# PongSat_Sen3.net
KiCad netlist of a schematic drawn in EAGLE
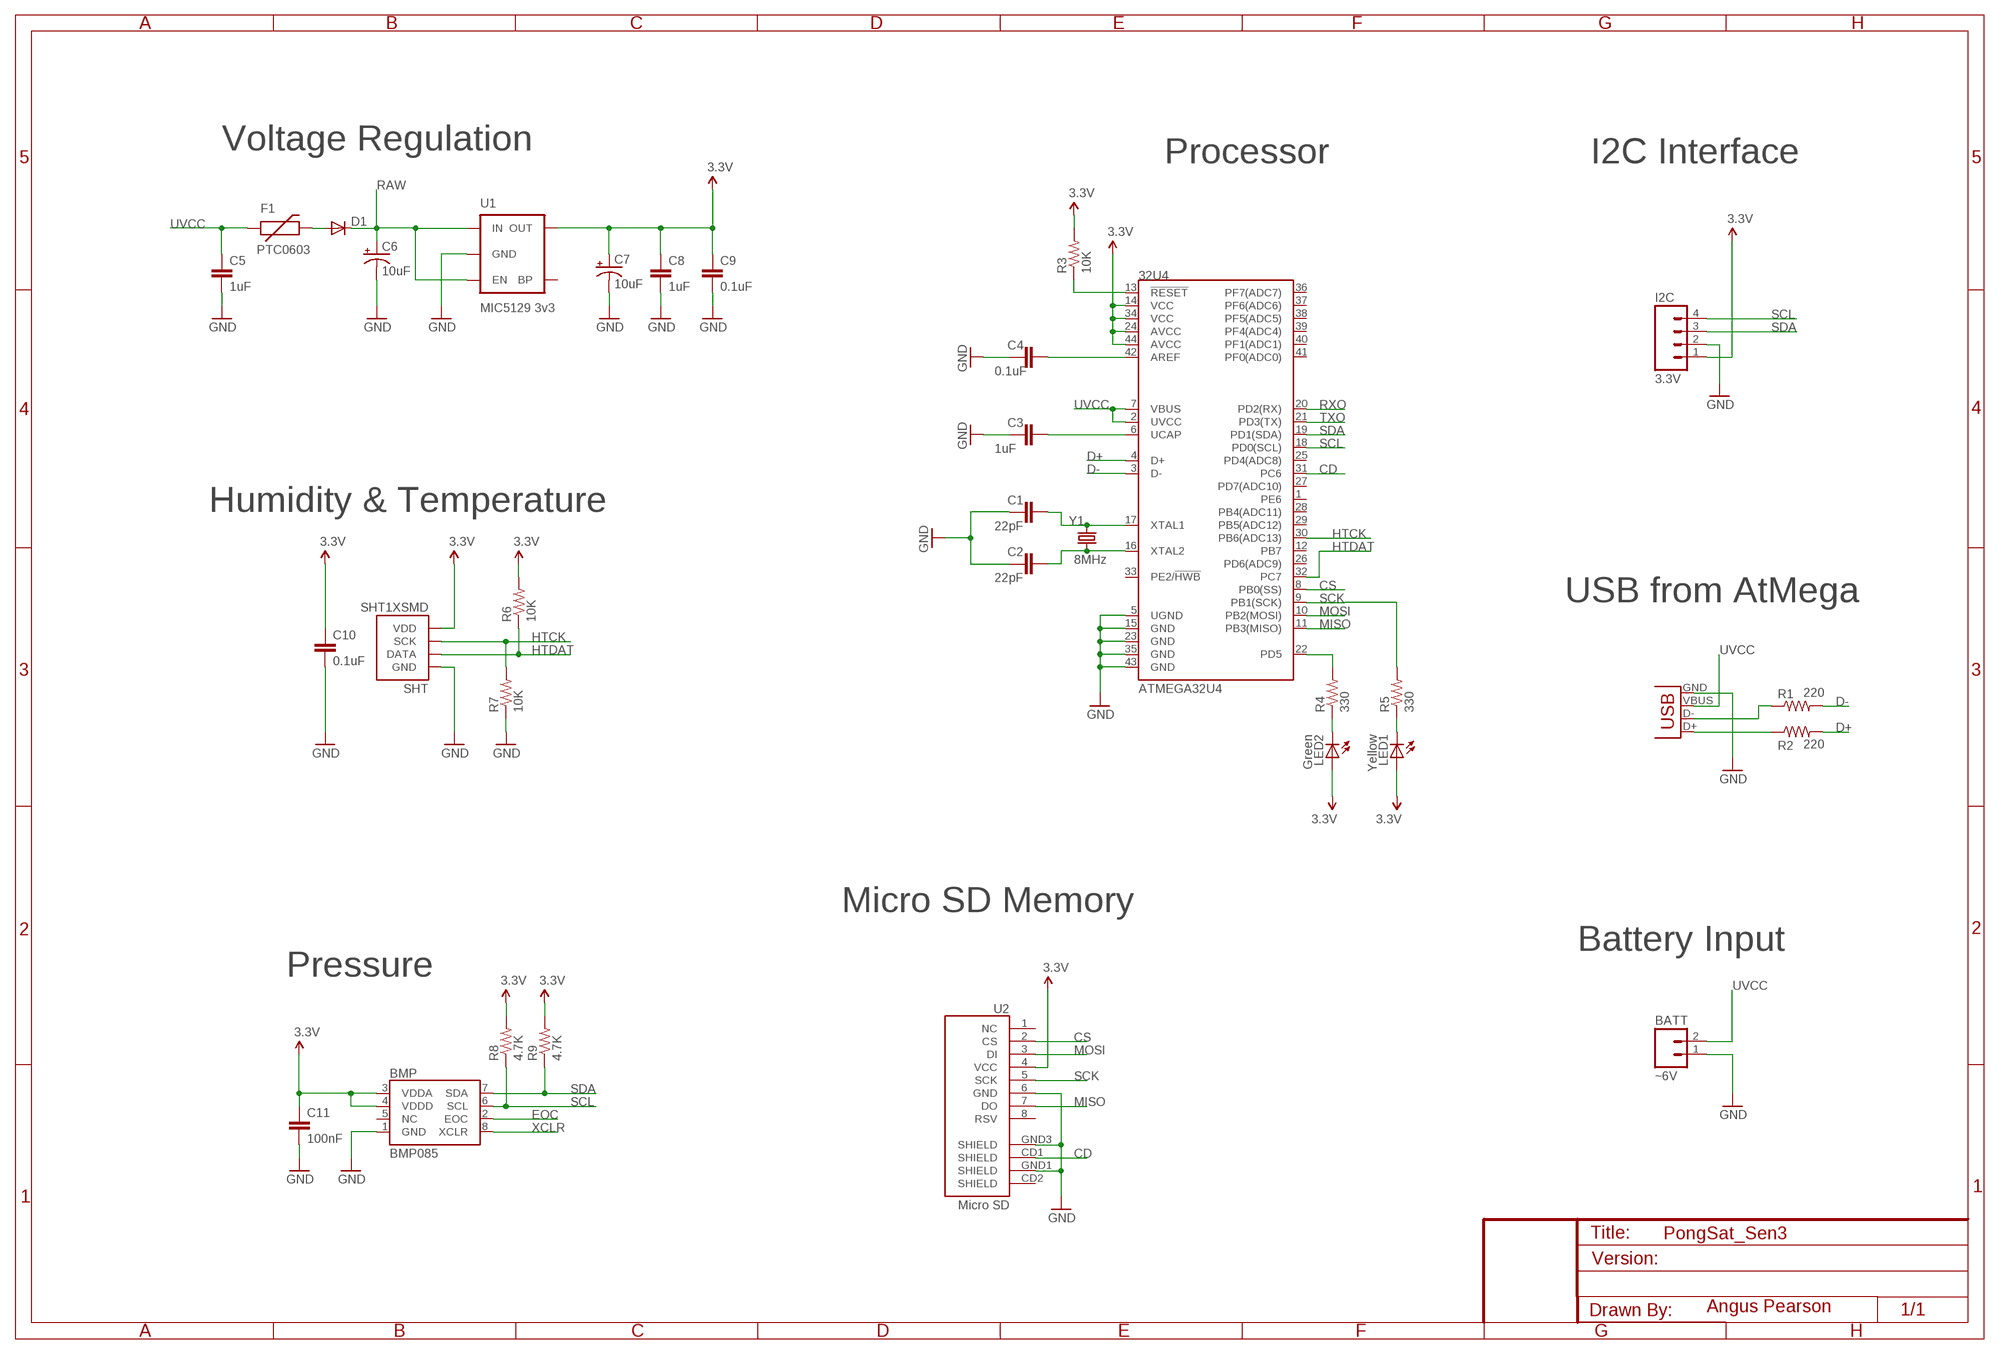
[diagram p0: schematic, sheet 1]

(export (version "E")
  (design (tool "Eeschema 10.0.6"))
  (components
    (comp (ref "32U4")
      (value "ATMEGA32U4")
      (footprint "eagle-import:QFN-44-NOPAD")
      (libsource (lib "eagle-import") (part "ATMEGA32U4QFN2"))
    )
    (comp (ref "BATT")
      (value "~6V")
      (footprint "eagle-import:1X02")
      (libsource (lib "eagle-import") (part "M02PTH"))
    )
    (comp (ref "BMP")
      (value "BMP085")
      (footprint "eagle-import:BMP085")
      (libsource (lib "eagle-import") (part "BMP085"))
    )
    (comp (ref "C1")
      (value "22pF")
      (footprint "eagle-import:0402-CAP")
      (libsource (lib "eagle-import") (part "CAP0402-CAP"))
    )
    (comp (ref "C2")
      (value "22pF")
      (footprint "eagle-import:0402-CAP")
      (libsource (lib "eagle-import") (part "CAP0402-CAP"))
    )
    (comp (ref "C3")
      (value "1uF")
      (footprint "eagle-import:0402-CAP")
      (libsource (lib "eagle-import") (part "CAP0402-CAP"))
    )
    (comp (ref "C4")
      (value "0.1uF")
      (footprint "eagle-import:0402-CAP")
      (libsource (lib "eagle-import") (part "CAP0402-CAP"))
    )
    (comp (ref "C5")
      (value "1uF")
      (footprint "eagle-import:0402-CAP")
      (libsource (lib "eagle-import") (part "CAP0402-CAP"))
    )
    (comp (ref "C6")
      (value "10uF")
      (footprint "eagle-import:EIA3216-KIT")
      (libsource (lib "eagle-import") (part "CAP_POL1206-KIT"))
    )
    (comp (ref "C7")
      (value "10uF")
      (footprint "eagle-import:EIA3216-KIT")
      (libsource (lib "eagle-import") (part "CAP_POL1206-KIT"))
    )
    (comp (ref "C8")
      (value "1uF")
      (footprint "eagle-import:0402-CAP")
      (libsource (lib "eagle-import") (part "CAP0402-CAP"))
    )
    (comp (ref "C9")
      (value "0.1uF")
      (footprint "eagle-import:0402-CAP")
      (libsource (lib "eagle-import") (part "CAP0402-CAP"))
    )
    (comp (ref "C10")
      (value "0.1uF")
      (footprint "eagle-import:0402-CAP")
      (libsource (lib "eagle-import") (part "CAP0402-CAP"))
    )
    (comp (ref "C11")
      (value "100nF")
      (footprint "eagle-import:0402-CAP")
      (libsource (lib "eagle-import") (part "CAP0402-CAP"))
    )
    (comp (ref "D1")
      (value "DIODESOT23")
      (footprint "eagle-import:SOT23-3")
      (libsource (lib "eagle-import") (part "DIODESOT23"))
    )
    (comp (ref "F1")
      (value "PTC0603")
      (footprint "eagle-import:0603")
      (libsource (lib "eagle-import") (part "PTC0603"))
    )
    (comp (ref "I2C")
      (value "3.3V")
      (footprint "eagle-import:1X04-SMD")
      (libsource (lib "eagle-import") (part "M04SMD"))
    )
    (comp (ref "LED1")
      (value "Yellow")
      (footprint "eagle-import:LED-0603")
      (libsource (lib "eagle-import") (part "LED0603"))
    )
    (comp (ref "LED2")
      (value "Green")
      (footprint "eagle-import:LED-0603")
      (libsource (lib "eagle-import") (part "LED0603"))
    )
    (comp (ref "R1")
      (value "220")
      (footprint "eagle-import:0402-RES")
      (libsource (lib "eagle-import") (part "RESISTOR0402-RES"))
    )
    (comp (ref "R2")
      (value "220")
      (footprint "eagle-import:0402-RES")
      (libsource (lib "eagle-import") (part "RESISTOR0402-RES"))
    )
    (comp (ref "R3")
      (value "10K")
      (footprint "eagle-import:0402-RES")
      (libsource (lib "eagle-import") (part "RESISTOR0402-RES"))
    )
    (comp (ref "R4")
      (value "330")
      (footprint "eagle-import:0402-RES")
      (libsource (lib "eagle-import") (part "RESISTOR0402-RES"))
    )
    (comp (ref "R5")
      (value "330")
      (footprint "eagle-import:0402-RES")
      (libsource (lib "eagle-import") (part "RESISTOR0402-RES"))
    )
    (comp (ref "R6")
      (value "10K")
      (footprint "eagle-import:0402-RES")
      (libsource (lib "eagle-import") (part "RESISTOR0402-RES"))
    )
    (comp (ref "R7")
      (value "10K")
      (footprint "eagle-import:0402-RES")
      (libsource (lib "eagle-import") (part "RESISTOR0402-RES"))
    )
    (comp (ref "R8")
      (value "4.7K")
      (footprint "eagle-import:0402-RES")
      (libsource (lib "eagle-import") (part "RESISTOR0402-RES"))
    )
    (comp (ref "R9")
      (value "4.7K")
      (footprint "eagle-import:0402-RES")
      (libsource (lib "eagle-import") (part "RESISTOR0402-RES"))
    )
    (comp (ref "SHT")
      (value "SHT1XSMD")
      (footprint "eagle-import:SHT1X")
      (libsource (lib "eagle-import") (part "SHT1XSMD"))
    )
    (comp (ref "U1")
      (value "MIC5129 3v3")
      (footprint "eagle-import:SOT23-5")
      (libsource (lib "eagle-import") (part "V_REG_MIC5219SMD"))
    )
    (comp (ref "U2")
      (value "Micro SD")
      (footprint "eagle-import:MICRO-SD-SOCKET-PP")
      (libsource (lib "eagle-import") (part "USD-SOCKETNEW"))
    )
    (comp (ref "X1")
      (value "USB-MICROB")
      (footprint "eagle-import:USB-MICROB")
      (libsource (lib "eagle-import") (part "USB-MICROB"))
    )
    (comp (ref "Y1")
      (value "8MHz")
      (footprint "eagle-import:CRYSTAL-SMD-5X3")
      (libsource (lib "eagle-import") (part "CRYSTAL5X3"))
    )
  )
  (nets
    (net (code "1") (name "/CD") (class "Default")
      (node (ref "32U4") (pin "31") (pinfunction "PC6_31") (pintype "bidirectional"))
      (node (ref "U2") (pin "CD1") (pinfunction "SHIELD_CD1") (pintype "bidirectional"))
    )
    (net (code "2") (name "/CS") (class "Default")
      (node (ref "32U4") (pin "8") (pinfunction "PB0(SS)_8") (pintype "bidirectional"))
      (node (ref "U2") (pin "2") (pinfunction "CS_2") (pintype "bidirectional"))
    )
    (net (code "3") (name "/D+") (class "Default")
      (node (ref "32U4") (pin "4") (pinfunction "D+_4") (pintype "bidirectional"))
      (node (ref "R2") (pin "2") (pinfunction "2_2") (pintype "passive"))
    )
    (net (code "4") (name "/D-") (class "Default")
      (node (ref "32U4") (pin "3") (pinfunction "D-_3") (pintype "bidirectional"))
      (node (ref "R1") (pin "2") (pinfunction "2_2") (pintype "passive"))
    )
    (net (code "5") (name "/EOC") (class "Default")
      (node (ref "BMP") (pin "2") (pinfunction "EOC_2") (pintype "output"))
    )
    (net (code "6") (name "/HTCK") (class "Default")
      (node (ref "32U4") (pin "30") (pinfunction "PB6(ADC13)_30") (pintype "bidirectional"))
      (node (ref "R7") (pin "2") (pinfunction "2_2") (pintype "passive"))
      (node (ref "SHT") (pin "3") (pinfunction "SCK_3") (pintype "input"))
    )
    (net (code "7") (name "/HTDAT") (class "Default")
      (node (ref "32U4") (pin "32") (pinfunction "PC7_32") (pintype "bidirectional"))
      (node (ref "R6") (pin "1") (pinfunction "1_1") (pintype "passive"))
      (node (ref "SHT") (pin "2") (pinfunction "DATA_2") (pintype "bidirectional"))
    )
    (net (code "8") (name "/MISO") (class "Default")
      (node (ref "32U4") (pin "11") (pinfunction "PB3(MISO)_11") (pintype "bidirectional"))
      (node (ref "U2") (pin "7") (pinfunction "DO_7") (pintype "bidirectional"))
    )
    (net (code "9") (name "/MOSI") (class "Default")
      (node (ref "32U4") (pin "10") (pinfunction "PB2(MOSI)_10") (pintype "bidirectional"))
      (node (ref "U2") (pin "3") (pinfunction "DI_3") (pintype "bidirectional"))
    )
    (net (code "10") (name "/RAW") (class "Default")
      (node (ref "C6") (pin "A") (pinfunction "+_A") (pintype "passive"))
      (node (ref "D1") (pin "3") (pinfunction "C_3") (pintype "passive"))
      (node (ref "U1") (pin "1") (pinfunction "IN_1") (pintype "input"))
      (node (ref "U1") (pin "3") (pinfunction "EN_3") (pintype "input"))
    )
    (net (code "11") (name "/RXO") (class "Default")
      (node (ref "32U4") (pin "20") (pinfunction "PD2(RX)_20") (pintype "bidirectional"))
    )
    (net (code "12") (name "/SCK") (class "Default")
      (node (ref "32U4") (pin "9") (pinfunction "PB1(SCK)_9") (pintype "bidirectional"))
      (node (ref "R5") (pin "2") (pinfunction "2_2") (pintype "passive"))
      (node (ref "U2") (pin "5") (pinfunction "SCK_5") (pintype "bidirectional"))
    )
    (net (code "13") (name "/SCL") (class "Default")
      (node (ref "32U4") (pin "18") (pinfunction "PD0(SCL)_18") (pintype "bidirectional"))
      (node (ref "BMP") (pin "6") (pinfunction "SCL_6") (pintype "input"))
      (node (ref "I2C") (pin "4") (pinfunction "4_4") (pintype "passive"))
      (node (ref "R8") (pin "1") (pinfunction "1_1") (pintype "passive"))
    )
    (net (code "14") (name "/SDA") (class "Default")
      (node (ref "32U4") (pin "19") (pinfunction "PD1(SDA)_19") (pintype "bidirectional"))
      (node (ref "BMP") (pin "7") (pinfunction "SDA_7") (pintype "bidirectional"))
      (node (ref "I2C") (pin "3") (pinfunction "3_3") (pintype "passive"))
      (node (ref "R9") (pin "1") (pinfunction "1_1") (pintype "passive"))
    )
    (net (code "15") (name "/TXO") (class "Default")
      (node (ref "32U4") (pin "21") (pinfunction "PD3(TX)_21") (pintype "bidirectional"))
    )
    (net (code "16") (name "/UVCC") (class "Default")
      (node (ref "32U4") (pin "2") (pinfunction "UVCC_2") (pintype "bidirectional"))
      (node (ref "32U4") (pin "7") (pinfunction "VBUS_7") (pintype "bidirectional"))
      (node (ref "BATT") (pin "2") (pinfunction "2_2") (pintype "passive"))
      (node (ref "C5") (pin "1") (pinfunction "1_1") (pintype "passive"))
      (node (ref "F1") (pin "1") (pinfunction "1_1") (pintype "bidirectional"))
      (node (ref "X1") (pin "VBUS") (pinfunction "VBUS_VBUS") (pintype "bidirectional"))
    )
    (net (code "17") (name "/XCLR") (class "Default")
      (node (ref "BMP") (pin "8") (pinfunction "XCLR_8") (pintype "input"))
    )
    (net (code "18") (name "3.3V") (class "Default")
      (node (ref "32U4") (pin "14") (pinfunction "VCC_14") (pintype "bidirectional"))
      (node (ref "32U4") (pin "24") (pinfunction "AVCC_24") (pintype "bidirectional"))
      (node (ref "32U4") (pin "34") (pinfunction "VCC_34") (pintype "bidirectional"))
      (node (ref "32U4") (pin "44") (pinfunction "AVCC_44") (pintype "bidirectional"))
      (node (ref "BMP") (pin "3") (pinfunction "VDDA_3") (pintype "power_in"))
      (node (ref "BMP") (pin "4") (pinfunction "VDDD_4") (pintype "power_in"))
      (node (ref "C10") (pin "1") (pinfunction "1_1") (pintype "passive"))
      (node (ref "C11") (pin "1") (pinfunction "1_1") (pintype "passive"))
      (node (ref "C7") (pin "A") (pinfunction "+_A") (pintype "passive"))
      (node (ref "C8") (pin "1") (pinfunction "1_1") (pintype "passive"))
      (node (ref "C9") (pin "1") (pinfunction "1_1") (pintype "passive"))
      (node (ref "I2C") (pin "1") (pinfunction "1_1") (pintype "passive"))
      (node (ref "LED1") (pin "A") (pinfunction "A_A") (pintype "passive"))
      (node (ref "LED2") (pin "A") (pinfunction "A_A") (pintype "passive"))
      (node (ref "R3") (pin "2") (pinfunction "2_2") (pintype "passive"))
      (node (ref "R6") (pin "2") (pinfunction "2_2") (pintype "passive"))
      (node (ref "R8") (pin "2") (pinfunction "2_2") (pintype "passive"))
      (node (ref "R9") (pin "2") (pinfunction "2_2") (pintype "passive"))
      (node (ref "SHT") (pin "4") (pinfunction "VDD_4") (pintype "power_in"))
      (node (ref "U1") (pin "5") (pinfunction "OUT_5") (pintype "passive"))
      (node (ref "U2") (pin "4") (pinfunction "VCC_4") (pintype "bidirectional"))
    )
    (net (code "19") (name "GND") (class "Default")
      (node (ref "32U4") (pin "15") (pinfunction "GND_15") (pintype "bidirectional"))
      (node (ref "32U4") (pin "23") (pinfunction "GND_23") (pintype "bidirectional"))
      (node (ref "32U4") (pin "35") (pinfunction "GND_35") (pintype "bidirectional"))
      (node (ref "32U4") (pin "43") (pinfunction "GND_43") (pintype "bidirectional"))
      (node (ref "32U4") (pin "5") (pinfunction "UGND_5") (pintype "bidirectional"))
      (node (ref "BATT") (pin "1") (pinfunction "1_1") (pintype "passive"))
      (node (ref "BMP") (pin "1") (pinfunction "GND_1") (pintype "power_in"))
      (node (ref "C1") (pin "1") (pinfunction "1_1") (pintype "passive"))
      (node (ref "C10") (pin "2") (pinfunction "2_2") (pintype "passive"))
      (node (ref "C11") (pin "2") (pinfunction "2_2") (pintype "passive"))
      (node (ref "C2") (pin "1") (pinfunction "1_1") (pintype "passive"))
      (node (ref "C3") (pin "1") (pinfunction "1_1") (pintype "passive"))
      (node (ref "C4") (pin "1") (pinfunction "1_1") (pintype "passive"))
      (node (ref "C5") (pin "2") (pinfunction "2_2") (pintype "passive"))
      (node (ref "C6") (pin "C") (pinfunction "-_C") (pintype "passive"))
      (node (ref "C7") (pin "C") (pinfunction "-_C") (pintype "passive"))
      (node (ref "C8") (pin "2") (pinfunction "2_2") (pintype "passive"))
      (node (ref "C9") (pin "2") (pinfunction "2_2") (pintype "passive"))
      (node (ref "I2C") (pin "2") (pinfunction "2_2") (pintype "passive"))
      (node (ref "R7") (pin "1") (pinfunction "1_1") (pintype "passive"))
      (node (ref "SHT") (pin "1") (pinfunction "GND_1") (pintype "power_in"))
      (node (ref "U1") (pin "2") (pinfunction "GND_2") (pintype "input"))
      (node (ref "U2") (pin "6") (pinfunction "GND_6") (pintype "bidirectional"))
      (node (ref "U2") (pin "GND1") (pinfunction "SHIELD_GND1") (pintype "bidirectional"))
      (node (ref "U2") (pin "GND3") (pinfunction "SHIELD_GND3") (pintype "bidirectional"))
      (node (ref "X1") (pin "GND") (pinfunction "GND_GND") (pintype "bidirectional"))
    )
    (net (code "20") (name "Net-(32U4-AREF)") (class "Default")
      (node (ref "32U4") (pin "42") (pinfunction "AREF_42") (pintype "bidirectional"))
      (node (ref "C4") (pin "2") (pinfunction "2_2") (pintype "passive"))
    )
    (net (code "21") (name "Net-(32U4-PD5)") (class "Default")
      (node (ref "32U4") (pin "22") (pinfunction "PD5_22") (pintype "bidirectional"))
      (node (ref "R4") (pin "2") (pinfunction "2_2") (pintype "passive"))
    )
    (net (code "22") (name "Net-(32U4-UCAP)") (class "Default")
      (node (ref "32U4") (pin "6") (pinfunction "UCAP_6") (pintype "bidirectional"))
      (node (ref "C3") (pin "2") (pinfunction "2_2") (pintype "passive"))
    )
    (net (code "23") (name "Net-(32U4-XTAL1)") (class "Default")
      (node (ref "32U4") (pin "17") (pinfunction "XTAL1_17") (pintype "bidirectional"))
      (node (ref "C1") (pin "2") (pinfunction "2_2") (pintype "passive"))
      (node (ref "Y1") (pin "3") (pinfunction "2_3") (pintype "passive"))
    )
    (net (code "24") (name "Net-(32U4-XTAL2)") (class "Default")
      (node (ref "32U4") (pin "16") (pinfunction "XTAL2_16") (pintype "bidirectional"))
      (node (ref "C2") (pin "2") (pinfunction "2_2") (pintype "passive"))
      (node (ref "Y1") (pin "1") (pinfunction "1_1") (pintype "passive"))
    )
    (net (code "25") (name "Net-(32U4-~{RESET})") (class "Default")
      (node (ref "32U4") (pin "13") (pinfunction "~{RESET}_13") (pintype "bidirectional"))
      (node (ref "R3") (pin "1") (pinfunction "1_1") (pintype "passive"))
    )
    (net (code "26") (name "Net-(D1-A)") (class "Default")
      (node (ref "D1") (pin "1") (pinfunction "A_1") (pintype "passive"))
      (node (ref "F1") (pin "2") (pinfunction "2_2") (pintype "bidirectional"))
    )
    (net (code "27") (name "Net-(LED1-PadC)") (class "Default")
      (node (ref "LED1") (pin "C") (pinfunction "C_C") (pintype "passive"))
      (node (ref "R5") (pin "1") (pinfunction "1_1") (pintype "passive"))
    )
    (net (code "28") (name "Net-(LED2-PadC)") (class "Default")
      (node (ref "LED2") (pin "C") (pinfunction "C_C") (pintype "passive"))
      (node (ref "R4") (pin "1") (pinfunction "1_1") (pintype "passive"))
    )
    (net (code "29") (name "Net-(R1-Pad1)") (class "Default")
      (node (ref "R1") (pin "1") (pinfunction "1_1") (pintype "passive"))
      (node (ref "X1") (pin "D-") (pinfunction "D-_D-") (pintype "bidirectional"))
    )
    (net (code "30") (name "Net-(R2-Pad1)") (class "Default")
      (node (ref "R2") (pin "1") (pinfunction "1_1") (pintype "passive"))
      (node (ref "X1") (pin "D+") (pinfunction "D+_D+") (pintype "bidirectional"))
    )
    (net (code "31") (name "unconnected-(32U4-PB4(ADC11)-Pad28)") (class "Default")
      (node (ref "32U4") (pin "28") (pinfunction "PB4(ADC11)_28") (pintype "bidirectional"))
    )
    (net (code "32") (name "unconnected-(32U4-PB5(ADC12)-Pad29)") (class "Default")
      (node (ref "32U4") (pin "29") (pinfunction "PB5(ADC12)_29") (pintype "bidirectional"))
    )
    (net (code "33") (name "unconnected-(32U4-PB7-Pad12)") (class "Default")
      (node (ref "32U4") (pin "12") (pinfunction "PB7_12") (pintype "bidirectional"))
    )
    (net (code "34") (name "unconnected-(32U4-PD4(ADC8)-Pad25)") (class "Default")
      (node (ref "32U4") (pin "25") (pinfunction "PD4(ADC8)_25") (pintype "bidirectional"))
    )
    (net (code "35") (name "unconnected-(32U4-PD6(ADC9)-Pad26)") (class "Default")
      (node (ref "32U4") (pin "26") (pinfunction "PD6(ADC9)_26") (pintype "bidirectional"))
    )
    (net (code "36") (name "unconnected-(32U4-PD7(ADC10)-Pad27)") (class "Default")
      (node (ref "32U4") (pin "27") (pinfunction "PD7(ADC10)_27") (pintype "bidirectional"))
    )
    (net (code "37") (name "unconnected-(32U4-PE2{slash}~{HWB}-Pad33)") (class "Default")
      (node (ref "32U4") (pin "33") (pinfunction "PE2/~{HWB}_33") (pintype "bidirectional"))
    )
    (net (code "38") (name "unconnected-(32U4-PE6-Pad1)") (class "Default")
      (node (ref "32U4") (pin "1") (pinfunction "PE6_1") (pintype "bidirectional"))
    )
    (net (code "39") (name "unconnected-(32U4-PF0(ADC0)-Pad41)") (class "Default")
      (node (ref "32U4") (pin "41") (pinfunction "PF0(ADC0)_41") (pintype "bidirectional"))
    )
    (net (code "40") (name "unconnected-(32U4-PF1(ADC1)-Pad40)") (class "Default")
      (node (ref "32U4") (pin "40") (pinfunction "PF1(ADC1)_40") (pintype "bidirectional"))
    )
    (net (code "41") (name "unconnected-(32U4-PF4(ADC4)-Pad39)") (class "Default")
      (node (ref "32U4") (pin "39") (pinfunction "PF4(ADC4)_39") (pintype "bidirectional"))
    )
    (net (code "42") (name "unconnected-(32U4-PF5(ADC5)-Pad38)") (class "Default")
      (node (ref "32U4") (pin "38") (pinfunction "PF5(ADC5)_38") (pintype "bidirectional"))
    )
    (net (code "43") (name "unconnected-(32U4-PF6(ADC6)-Pad37)") (class "Default")
      (node (ref "32U4") (pin "37") (pinfunction "PF6(ADC6)_37") (pintype "bidirectional"))
    )
    (net (code "44") (name "unconnected-(32U4-PF7(ADC7)-Pad36)") (class "Default")
      (node (ref "32U4") (pin "36") (pinfunction "PF7(ADC7)_36") (pintype "bidirectional"))
    )
    (net (code "45") (name "unconnected-(BMP-NC-Pad5)") (class "Default")
      (node (ref "BMP") (pin "5") (pinfunction "NC_5") (pintype "bidirectional"))
    )
    (net (code "46") (name "unconnected-(U1-BP-Pad4)") (class "Default")
      (node (ref "U1") (pin "4") (pinfunction "BP_4") (pintype "input"))
    )
    (net (code "47") (name "unconnected-(U2-NC-Pad1)") (class "Default")
      (node (ref "U2") (pin "1") (pinfunction "NC_1") (pintype "bidirectional"))
    )
    (net (code "48") (name "unconnected-(U2-RSV-Pad8)") (class "Default")
      (node (ref "U2") (pin "8") (pinfunction "RSV_8") (pintype "bidirectional"))
    )
    (net (code "49") (name "unconnected-(U2-SHIELD-PadCD2)") (class "Default")
      (node (ref "U2") (pin "CD2") (pinfunction "SHIELD_CD2") (pintype "bidirectional"))
    )
  )
)
